# leds.net
KiCad netlist of a schematic drawn in Altium Designer
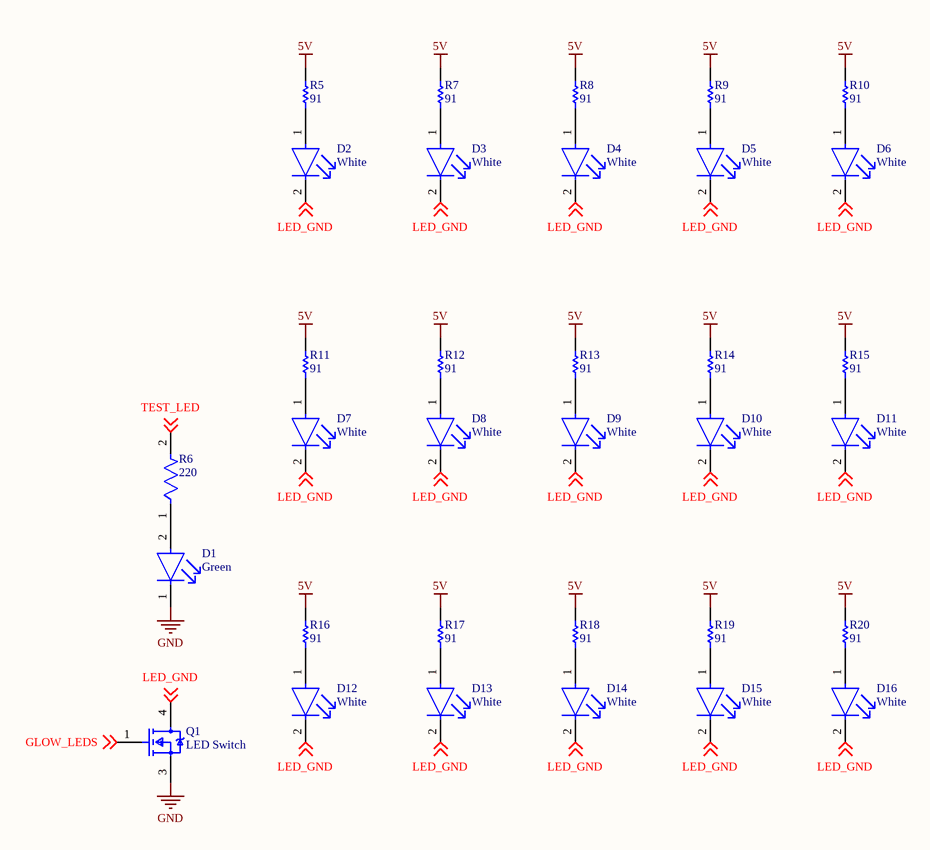
[diagram p0: leds.SchDoc]

(export (version "E")
  (design (tool "Eeschema 10.0.6"))
  (components
    (comp (ref "D1")
      (value "Green")
      (footprint "FP-APTD3216CGCK-MFG")
      (description "LED GREEN CLEAR 2SMD")
      (fields (field (name "MPN") "APTD3216CGCK"))
      (libsource (lib "Altium Content Vault") (part "8706943c75ba83719d021d2fdc84c58"))
    )
    (comp (ref "D2")
      (value "White")
      (footprint "FP-QBLP650-IW-MFG")
      (description "LED WHITE CLEAR 1206 SMD")
      (fields (field (name "MPN") "QBLP650-IW"))
      (libsource (lib "Altium Content Vault") (part "ab1c01a81903e929fc6c44469aada92"))
    )
    (comp (ref "D3")
      (value "White")
      (footprint "FP-QBLP650-IW-MFG")
      (description "LED WHITE CLEAR 1206 SMD")
      (fields (field (name "MPN") "QBLP650-IW"))
      (libsource (lib "Altium Content Vault") (part "ab1c01a81903e929fc6c44469aada92"))
    )
    (comp (ref "D4")
      (value "White")
      (footprint "FP-QBLP650-IW-MFG")
      (description "LED WHITE CLEAR 1206 SMD")
      (fields (field (name "MPN") "QBLP650-IW"))
      (libsource (lib "Altium Content Vault") (part "ab1c01a81903e929fc6c44469aada92"))
    )
    (comp (ref "D5")
      (value "White")
      (footprint "FP-QBLP650-IW-MFG")
      (description "LED WHITE CLEAR 1206 SMD")
      (fields (field (name "MPN") "QBLP650-IW"))
      (libsource (lib "Altium Content Vault") (part "ab1c01a81903e929fc6c44469aada92"))
    )
    (comp (ref "D6")
      (value "White")
      (footprint "FP-QBLP650-IW-MFG")
      (description "LED WHITE CLEAR 1206 SMD")
      (fields (field (name "MPN") "QBLP650-IW"))
      (libsource (lib "Altium Content Vault") (part "ab1c01a81903e929fc6c44469aada92"))
    )
    (comp (ref "D7")
      (value "White")
      (footprint "FP-QBLP650-IW-MFG")
      (description "LED WHITE CLEAR 1206 SMD")
      (fields (field (name "MPN") "QBLP650-IW"))
      (libsource (lib "Altium Content Vault") (part "ab1c01a81903e929fc6c44469aada92"))
    )
    (comp (ref "D8")
      (value "White")
      (footprint "FP-QBLP650-IW-MFG")
      (description "LED WHITE CLEAR 1206 SMD")
      (fields (field (name "MPN") "QBLP650-IW"))
      (libsource (lib "Altium Content Vault") (part "ab1c01a81903e929fc6c44469aada92"))
    )
    (comp (ref "D9")
      (value "White")
      (footprint "FP-QBLP650-IW-MFG")
      (description "LED WHITE CLEAR 1206 SMD")
      (fields (field (name "MPN") "QBLP650-IW"))
      (libsource (lib "Altium Content Vault") (part "ab1c01a81903e929fc6c44469aada92"))
    )
    (comp (ref "D10")
      (value "White")
      (footprint "FP-QBLP650-IW-MFG")
      (description "LED WHITE CLEAR 1206 SMD")
      (fields (field (name "MPN") "QBLP650-IW"))
      (libsource (lib "Altium Content Vault") (part "ab1c01a81903e929fc6c44469aada92"))
    )
    (comp (ref "D11")
      (value "White")
      (footprint "FP-QBLP650-IW-MFG")
      (description "LED WHITE CLEAR 1206 SMD")
      (fields (field (name "MPN") "QBLP650-IW"))
      (libsource (lib "Altium Content Vault") (part "ab1c01a81903e929fc6c44469aada92"))
    )
    (comp (ref "D12")
      (value "White")
      (footprint "FP-QBLP650-IW-MFG")
      (description "LED WHITE CLEAR 1206 SMD")
      (fields (field (name "MPN") "QBLP650-IW"))
      (libsource (lib "Altium Content Vault") (part "ab1c01a81903e929fc6c44469aada92"))
    )
    (comp (ref "D13")
      (value "White")
      (footprint "FP-QBLP650-IW-MFG")
      (description "LED WHITE CLEAR 1206 SMD")
      (fields (field (name "MPN") "QBLP650-IW"))
      (libsource (lib "Altium Content Vault") (part "ab1c01a81903e929fc6c44469aada92"))
    )
    (comp (ref "D14")
      (value "White")
      (footprint "FP-QBLP650-IW-MFG")
      (description "LED WHITE CLEAR 1206 SMD")
      (fields (field (name "MPN") "QBLP650-IW"))
      (libsource (lib "Altium Content Vault") (part "ab1c01a81903e929fc6c44469aada92"))
    )
    (comp (ref "D15")
      (value "White")
      (footprint "FP-QBLP650-IW-MFG")
      (description "LED WHITE CLEAR 1206 SMD")
      (fields (field (name "MPN") "QBLP650-IW"))
      (libsource (lib "Altium Content Vault") (part "ab1c01a81903e929fc6c44469aada92"))
    )
    (comp (ref "D16")
      (value "White")
      (footprint "FP-QBLP650-IW-MFG")
      (description "LED WHITE CLEAR 1206 SMD")
      (fields (field (name "MPN") "QBLP650-IW"))
      (libsource (lib "Altium Content Vault") (part "ab1c01a81903e929fc6c44469aada92"))
    )
    (comp (ref "Q1")
      (value "LED Switch")
      (footprint "FP-PG-TO263-3-MFG")
      (description "MOSFET N-CH 100V 17A D2PAK")
      (fields
        (field (name "MANUFACTURER PART NUMBER") "IRF530NSTRLPBF")
        (field (name "OCTOPART") "https://octopart.com/irf530nstrlpbf-infineon-65873402")
      )
      (libsource (lib "Altium Content Vault") (part "cdf1c68f84cb049e5ebc85739c3fcf6"))
    )
    (comp (ref "R5")
      (value "91")
      (footprint "RESC2013X70X40NL20T20")
      (fields (field (name "PART NUMBER") "ERJ-6GEYJ910V") (field (name "MANUFACTURER") "Panasonic"))
      (libsource (lib "Altium Content Vault") (part "RES"))
    )
    (comp (ref "R6")
      (value "220")
      (footprint "FP-CRCW0805-e3-MFG")
      (description "RES Thick Film, 220Ω, 1%, 0.125W, 100ppm/°C, 0805")
      (fields (field (name "TOLERANCE") "1%") (field (name "MPN") "CRCW0805220RFKEA"))
      (libsource (lib "Altium Content Vault") (part "1029c3af85768c4190bb7ad29bc67b5"))
    )
    (comp (ref "R7")
      (value "91")
      (footprint "RESC2013X70X40NL20T20")
      (fields (field (name "PART NUMBER") "ERJ-6GEYJ910V") (field (name "MANUFACTURER") "Panasonic"))
      (libsource (lib "Altium Content Vault") (part "RES"))
    )
    (comp (ref "R8")
      (value "91")
      (footprint "RESC2013X70X40NL20T20")
      (fields (field (name "PART NUMBER") "ERJ-6GEYJ910V") (field (name "MANUFACTURER") "Panasonic"))
      (libsource (lib "Altium Content Vault") (part "RES"))
    )
    (comp (ref "R9")
      (value "91")
      (footprint "RESC2013X70X40NL20T20")
      (fields (field (name "PART NUMBER") "ERJ-6GEYJ910V") (field (name "MANUFACTURER") "Panasonic"))
      (libsource (lib "Altium Content Vault") (part "RES"))
    )
    (comp (ref "R10")
      (value "91")
      (footprint "RESC2013X70X40NL20T20")
      (fields (field (name "PART NUMBER") "ERJ-6GEYJ910V") (field (name "MANUFACTURER") "Panasonic"))
      (libsource (lib "Altium Content Vault") (part "RES"))
    )
    (comp (ref "R11")
      (value "91")
      (footprint "RESC2013X70X40NL20T20")
      (fields (field (name "PART NUMBER") "ERJ-6GEYJ910V") (field (name "MANUFACTURER") "Panasonic"))
      (libsource (lib "Altium Content Vault") (part "RES"))
    )
    (comp (ref "R12")
      (value "91")
      (footprint "RESC2013X70X40NL20T20")
      (fields (field (name "PART NUMBER") "ERJ-6GEYJ910V") (field (name "MANUFACTURER") "Panasonic"))
      (libsource (lib "Altium Content Vault") (part "RES"))
    )
    (comp (ref "R13")
      (value "91")
      (footprint "RESC2013X70X40NL20T20")
      (fields (field (name "PART NUMBER") "ERJ-6GEYJ910V") (field (name "MANUFACTURER") "Panasonic"))
      (libsource (lib "Altium Content Vault") (part "RES"))
    )
    (comp (ref "R14")
      (value "91")
      (footprint "RESC2013X70X40NL20T20")
      (fields (field (name "PART NUMBER") "ERJ-6GEYJ910V") (field (name "MANUFACTURER") "Panasonic"))
      (libsource (lib "Altium Content Vault") (part "RES"))
    )
    (comp (ref "R15")
      (value "91")
      (footprint "RESC2013X70X40NL20T20")
      (fields (field (name "PART NUMBER") "ERJ-6GEYJ910V") (field (name "MANUFACTURER") "Panasonic"))
      (libsource (lib "Altium Content Vault") (part "RES"))
    )
    (comp (ref "R16")
      (value "91")
      (footprint "RESC2013X70X40NL20T20")
      (fields (field (name "PART NUMBER") "ERJ-6GEYJ910V") (field (name "MANUFACTURER") "Panasonic"))
      (libsource (lib "Altium Content Vault") (part "RES"))
    )
    (comp (ref "R17")
      (value "91")
      (footprint "RESC2013X70X40NL20T20")
      (fields (field (name "PART NUMBER") "ERJ-6GEYJ910V") (field (name "MANUFACTURER") "Panasonic"))
      (libsource (lib "Altium Content Vault") (part "RES"))
    )
    (comp (ref "R18")
      (value "91")
      (footprint "RESC2013X70X40NL20T20")
      (fields (field (name "PART NUMBER") "ERJ-6GEYJ910V") (field (name "MANUFACTURER") "Panasonic"))
      (libsource (lib "Altium Content Vault") (part "RES"))
    )
    (comp (ref "R19")
      (value "91")
      (footprint "RESC2013X70X40NL20T20")
      (fields (field (name "PART NUMBER") "ERJ-6GEYJ910V") (field (name "MANUFACTURER") "Panasonic"))
      (libsource (lib "Altium Content Vault") (part "RES"))
    )
    (comp (ref "R20")
      (value "91")
      (footprint "RESC2013X70X40NL20T20")
      (fields (field (name "PART NUMBER") "ERJ-6GEYJ910V") (field (name "MANUFACTURER") "Panasonic"))
      (libsource (lib "Altium Content Vault") (part "RES"))
    )
  )
  (nets
    (net (code "1") (name "5V") (class "Default")
      (node (ref "R10") (pin "2") (pinfunction "2_2") (pintype "passive"))
      (node (ref "R11") (pin "2") (pinfunction "2_2") (pintype "passive"))
      (node (ref "R12") (pin "2") (pinfunction "2_2") (pintype "passive"))
      (node (ref "R13") (pin "2") (pinfunction "2_2") (pintype "passive"))
      (node (ref "R14") (pin "2") (pinfunction "2_2") (pintype "passive"))
      (node (ref "R15") (pin "2") (pinfunction "2_2") (pintype "passive"))
      (node (ref "R16") (pin "2") (pinfunction "2_2") (pintype "passive"))
      (node (ref "R17") (pin "2") (pinfunction "2_2") (pintype "passive"))
      (node (ref "R18") (pin "2") (pinfunction "2_2") (pintype "passive"))
      (node (ref "R19") (pin "2") (pinfunction "2_2") (pintype "passive"))
      (node (ref "R20") (pin "2") (pinfunction "2_2") (pintype "passive"))
      (node (ref "R5") (pin "2") (pinfunction "2_2") (pintype "passive"))
      (node (ref "R7") (pin "2") (pinfunction "2_2") (pintype "passive"))
      (node (ref "R8") (pin "2") (pinfunction "2_2") (pintype "passive"))
      (node (ref "R9") (pin "2") (pinfunction "2_2") (pintype "passive"))
    )
    (net (code "2") (name "GLOW_LEDS") (class "Default")
      (node (ref "Q1") (pin "1") (pinfunction "G_1") (pintype "passive"))
    )
    (net (code "3") (name "GND") (class "Default")
      (node (ref "D1") (pin "1") (pinfunction "C_1") (pintype "passive"))
      (node (ref "Q1") (pin "3") (pinfunction "S_3") (pintype "passive"))
    )
    (net (code "4") (name "LED_GND") (class "Default")
      (node (ref "D10") (pin "2") (pinfunction "C_2") (pintype "passive"))
      (node (ref "D11") (pin "2") (pinfunction "C_2") (pintype "passive"))
      (node (ref "D12") (pin "2") (pinfunction "C_2") (pintype "passive"))
      (node (ref "D13") (pin "2") (pinfunction "C_2") (pintype "passive"))
      (node (ref "D14") (pin "2") (pinfunction "C_2") (pintype "passive"))
      (node (ref "D15") (pin "2") (pinfunction "C_2") (pintype "passive"))
      (node (ref "D16") (pin "2") (pinfunction "C_2") (pintype "passive"))
      (node (ref "D2") (pin "2") (pinfunction "C_2") (pintype "passive"))
      (node (ref "D3") (pin "2") (pinfunction "C_2") (pintype "passive"))
      (node (ref "D4") (pin "2") (pinfunction "C_2") (pintype "passive"))
      (node (ref "D5") (pin "2") (pinfunction "C_2") (pintype "passive"))
      (node (ref "D6") (pin "2") (pinfunction "C_2") (pintype "passive"))
      (node (ref "D7") (pin "2") (pinfunction "C_2") (pintype "passive"))
      (node (ref "D8") (pin "2") (pinfunction "C_2") (pintype "passive"))
      (node (ref "D9") (pin "2") (pinfunction "C_2") (pintype "passive"))
      (node (ref "Q1") (pin "4") (pinfunction "D_4") (pintype "passive"))
    )
    (net (code "5") (name "Net-(D1-A)") (class "Default")
      (node (ref "D1") (pin "2") (pinfunction "A_2") (pintype "passive"))
      (node (ref "R6") (pin "1") (pinfunction "1_1") (pintype "passive"))
    )
    (net (code "6") (name "Net-(D2-A)") (class "Default")
      (node (ref "D2") (pin "1") (pinfunction "A_1") (pintype "passive"))
      (node (ref "R5") (pin "1") (pinfunction "1_1") (pintype "passive"))
    )
    (net (code "7") (name "Net-(D3-A)") (class "Default")
      (node (ref "D3") (pin "1") (pinfunction "A_1") (pintype "passive"))
      (node (ref "R7") (pin "1") (pinfunction "1_1") (pintype "passive"))
    )
    (net (code "8") (name "Net-(D4-A)") (class "Default")
      (node (ref "D4") (pin "1") (pinfunction "A_1") (pintype "passive"))
      (node (ref "R8") (pin "1") (pinfunction "1_1") (pintype "passive"))
    )
    (net (code "9") (name "Net-(D5-A)") (class "Default")
      (node (ref "D5") (pin "1") (pinfunction "A_1") (pintype "passive"))
      (node (ref "R9") (pin "1") (pinfunction "1_1") (pintype "passive"))
    )
    (net (code "10") (name "Net-(D6-A)") (class "Default")
      (node (ref "D6") (pin "1") (pinfunction "A_1") (pintype "passive"))
      (node (ref "R10") (pin "1") (pinfunction "1_1") (pintype "passive"))
    )
    (net (code "11") (name "Net-(D7-A)") (class "Default")
      (node (ref "D7") (pin "1") (pinfunction "A_1") (pintype "passive"))
      (node (ref "R11") (pin "1") (pinfunction "1_1") (pintype "passive"))
    )
    (net (code "12") (name "Net-(D8-A)") (class "Default")
      (node (ref "D8") (pin "1") (pinfunction "A_1") (pintype "passive"))
      (node (ref "R12") (pin "1") (pinfunction "1_1") (pintype "passive"))
    )
    (net (code "13") (name "Net-(D9-A)") (class "Default")
      (node (ref "D9") (pin "1") (pinfunction "A_1") (pintype "passive"))
      (node (ref "R13") (pin "1") (pinfunction "1_1") (pintype "passive"))
    )
    (net (code "14") (name "Net-(D10-A)") (class "Default")
      (node (ref "D10") (pin "1") (pinfunction "A_1") (pintype "passive"))
      (node (ref "R14") (pin "1") (pinfunction "1_1") (pintype "passive"))
    )
    (net (code "15") (name "Net-(D11-A)") (class "Default")
      (node (ref "D11") (pin "1") (pinfunction "A_1") (pintype "passive"))
      (node (ref "R15") (pin "1") (pinfunction "1_1") (pintype "passive"))
    )
    (net (code "16") (name "Net-(D12-A)") (class "Default")
      (node (ref "D12") (pin "1") (pinfunction "A_1") (pintype "passive"))
      (node (ref "R16") (pin "1") (pinfunction "1_1") (pintype "passive"))
    )
    (net (code "17") (name "Net-(D13-A)") (class "Default")
      (node (ref "D13") (pin "1") (pinfunction "A_1") (pintype "passive"))
      (node (ref "R17") (pin "1") (pinfunction "1_1") (pintype "passive"))
    )
    (net (code "18") (name "Net-(D14-A)") (class "Default")
      (node (ref "D14") (pin "1") (pinfunction "A_1") (pintype "passive"))
      (node (ref "R18") (pin "1") (pinfunction "1_1") (pintype "passive"))
    )
    (net (code "19") (name "Net-(D15-A)") (class "Default")
      (node (ref "D15") (pin "1") (pinfunction "A_1") (pintype "passive"))
      (node (ref "R19") (pin "1") (pinfunction "1_1") (pintype "passive"))
    )
    (net (code "20") (name "Net-(D16-A)") (class "Default")
      (node (ref "D16") (pin "1") (pinfunction "A_1") (pintype "passive"))
      (node (ref "R20") (pin "1") (pinfunction "1_1") (pintype "passive"))
    )
    (net (code "21") (name "TEST_LED") (class "Default")
      (node (ref "R6") (pin "2") (pinfunction "2_2") (pintype "passive"))
    )
  )
)
